# clock_module.net
KiCad netlist of a schematic drawn in EAGLE
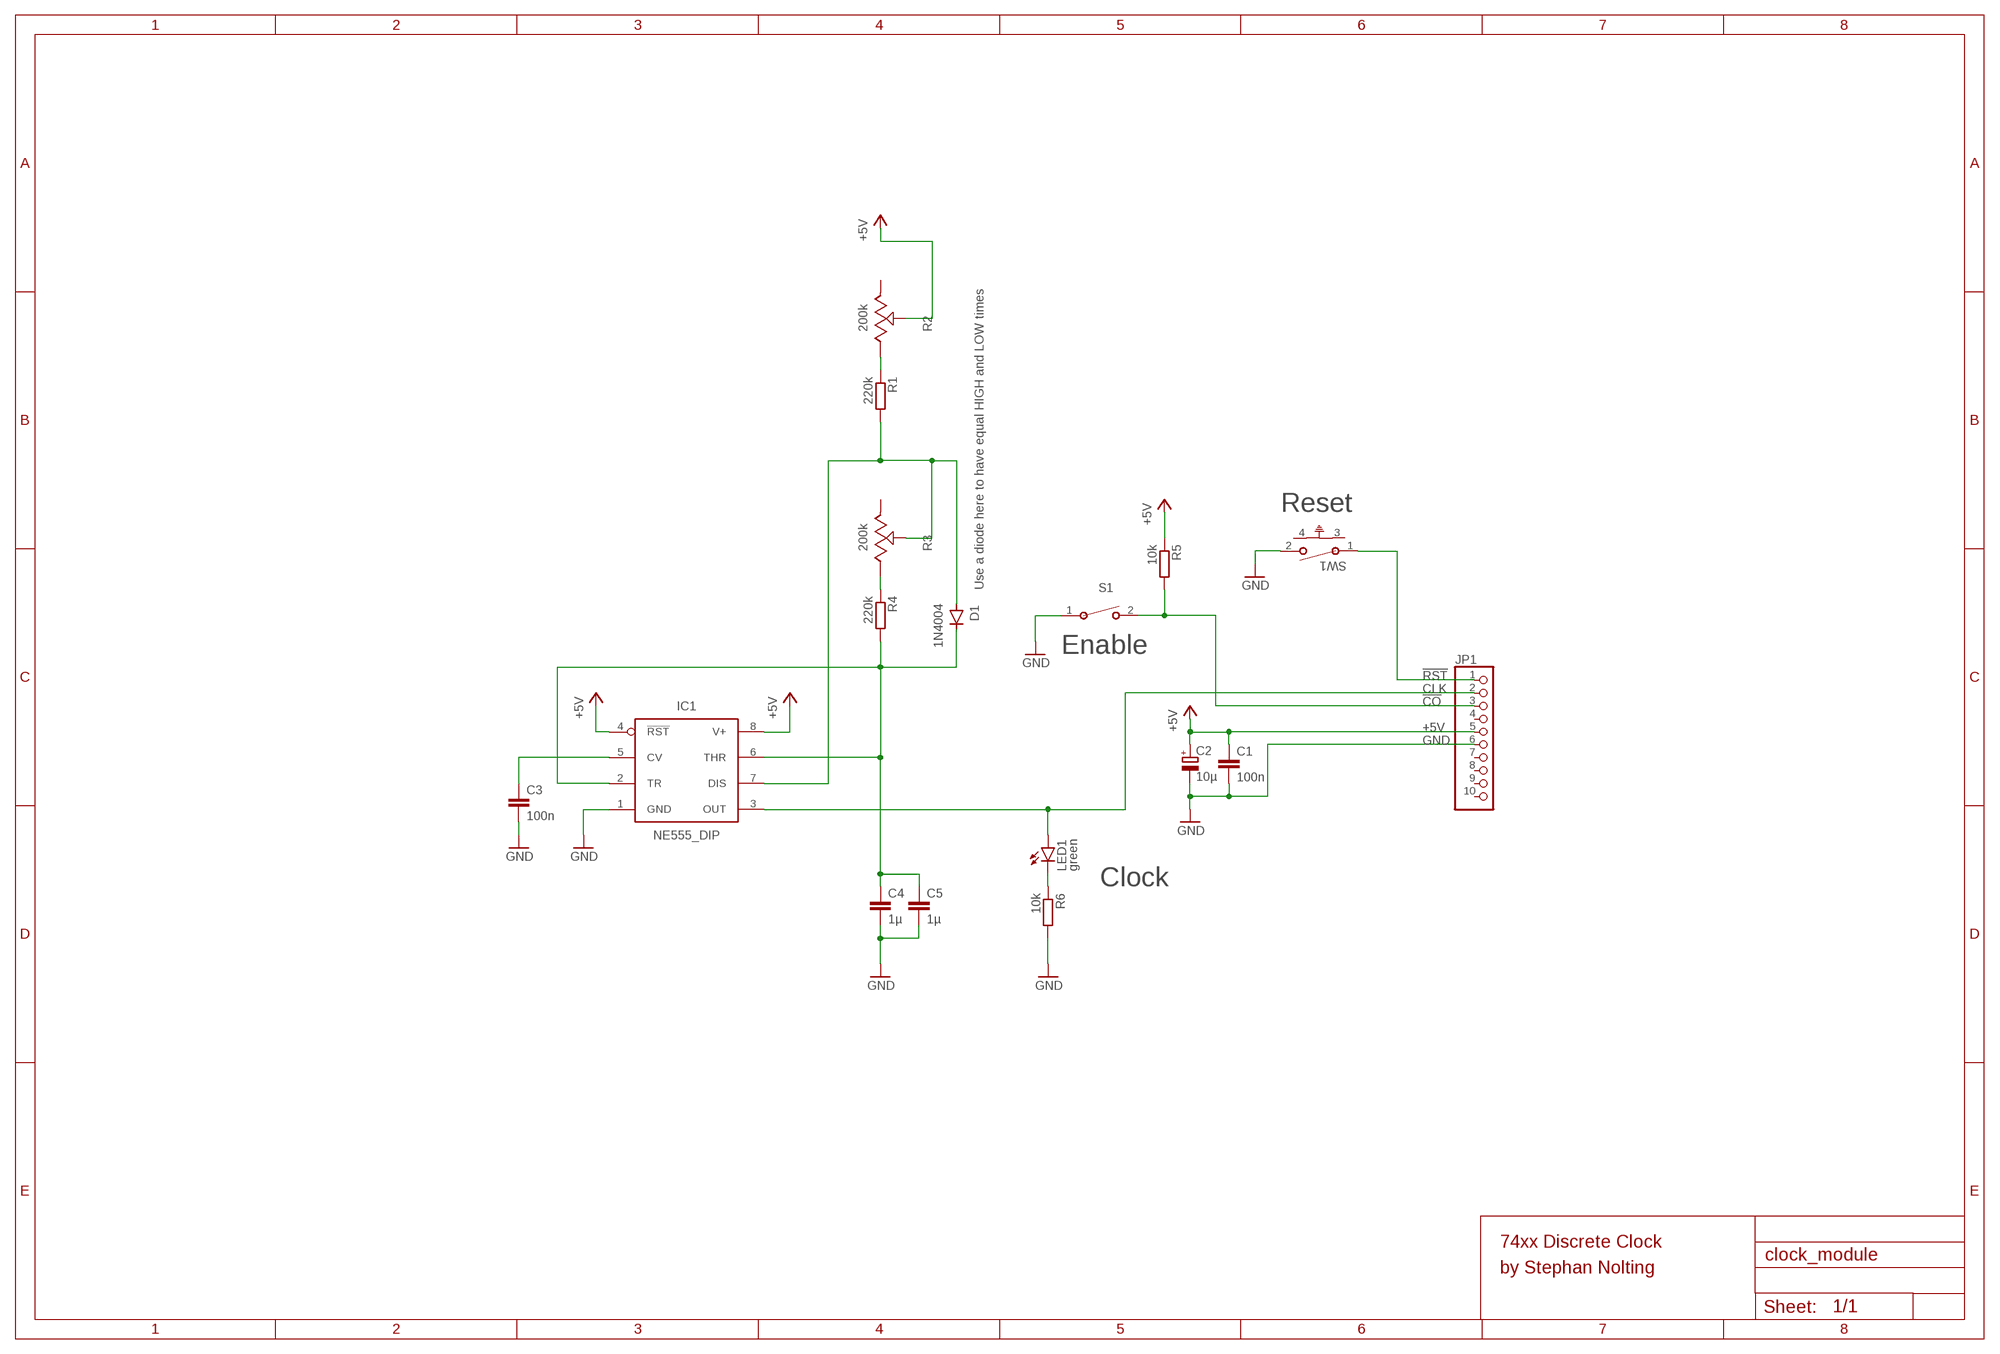
[diagram p0: schematic, sheet 1]

(export (version "E")
  (design (tool "Eeschema 10.0.6"))
  (components
    (comp (ref "C1")
      (value "100n")
      (footprint "eagle-import:C025-024X044")
      (libsource (lib "eagle-import") (part "C-EU025-024X044"))
    )
    (comp (ref "C2")
      (value "10µ")
      (footprint "eagle-import:E2-5")
      (libsource (lib "eagle-import") (part "CPOL-EUE2-5"))
    )
    (comp (ref "C3")
      (value "100n")
      (footprint "eagle-import:C025-024X044")
      (libsource (lib "eagle-import") (part "C-EU025-024X044"))
    )
    (comp (ref "C4")
      (value "1µ")
      (footprint "eagle-import:C025-024X044")
      (libsource (lib "eagle-import") (part "C-EU025-024X044"))
    )
    (comp (ref "C5")
      (value "1µ")
      (footprint "eagle-import:C025-024X044")
      (libsource (lib "eagle-import") (part "C-EU025-024X044"))
    )
    (comp (ref "D1")
      (value "1N4004")
      (footprint "eagle-import:DO-41")
      (fields
        (field (name "DIGIKEY_PART_NUMBER") "1N4004MSCT-ND")
        (field (name "MANUFACTURER") "Micro Commercial Co")
        (field (name "CREATED_BY") "PCBLayout.com")
      )
      (libsource (lib "eagle-import") (part "1N4004"))
    )
    (comp (ref "IC1")
      (value "NE555_DIP")
      (footprint "eagle-import:DIP826W53P254L959H508Q8B")
      (fields (field (name "MANUFACTURER") "Texas Instruments ") (field (name "MPN") "NE555P "))
      (libsource (lib "eagle-import") (part "555_DIPNE"))
    )
    (comp (ref "JP1")
      (value "PINHD-1X10/90")
      (footprint "eagle-import:1X10_90")
      (libsource (lib "eagle-import") (part "PINHD-1X10/90"))
    )
    (comp (ref "LED1")
      (value "green")
      (footprint "eagle-import:LED3MM")
      (libsource (lib "eagle-import") (part "LED3MM"))
    )
    (comp (ref "R1")
      (value "220k")
      (footprint "eagle-import:0204_7")
      (libsource (lib "eagle-import") (part "R-EU_0204/7"))
    )
    (comp (ref "R2")
      (value "200k")
      (footprint "eagle-import:3310Y-001-104L-ND")
      (fields
        (field (name "DIGIKEY_PARTNO") "3310Y-001-104L-ND")
        (field (name "MANUFACTURER") "Bourns Inc.")
        (field (name "MPN") "3310Y-001-104L")
        (field (name "CREATED_BY") " PCBLayout.com")
      )
      (libsource (lib "eagle-import") (part "3310Y-001-104L"))
    )
    (comp (ref "R3")
      (value "200k")
      (footprint "eagle-import:3310Y-001-104L-ND")
      (fields
        (field (name "DIGIKEY_PARTNO") "3310Y-001-104L-ND")
        (field (name "MANUFACTURER") "Bourns Inc.")
        (field (name "MPN") "3310Y-001-104L")
        (field (name "CREATED_BY") " PCBLayout.com")
      )
      (libsource (lib "eagle-import") (part "3310Y-001-104L"))
    )
    (comp (ref "R4")
      (value "220k")
      (footprint "eagle-import:0204_7")
      (libsource (lib "eagle-import") (part "R-EU_0204/7"))
    )
    (comp (ref "R5")
      (value "10k")
      (footprint "eagle-import:0204_7")
      (libsource (lib "eagle-import") (part "R-EU_0204/7"))
    )
    (comp (ref "R6")
      (value "10k")
      (footprint "eagle-import:0204_7")
      (libsource (lib "eagle-import") (part "R-EU_0204/7"))
    )
    (comp (ref "S1")
      (value "1825966-1")
      (footprint "eagle-import:SWDIP2_256X170P100")
      (fields (field (name "COPYRIGHT") "Copyright (C) 2016 Accelerated Designs. All rights reserved"))
      (libsource (lib "eagle-import") (part "1825966-1"))
    )
    (comp (ref "SW1")
      (value "1-1825027-4")
      (footprint "eagle-import:SW2_1825027-E")
      (fields (field (name "COPYRIGHT") "Copyright (C) 2016 Accelerated Designs. All rights reserved"))
      (libsource (lib "eagle-import") (part "1-1825027-4"))
    )
  )
  (nets
    (net (code "1") (name "+5V") (class "Default")
      (node (ref "C1") (pin "1") (pinfunction "1_1") (pintype "passive"))
      (node (ref "C2") (pin "+") (pinfunction "+_+") (pintype "passive"))
      (node (ref "IC1") (pin "4") (pinfunction "~{RST}_4") (pintype "input"))
      (node (ref "IC1") (pin "8") (pinfunction "V+_8") (pintype "power_in"))
      (node (ref "JP1") (pin "5") (pinfunction "5_5") (pintype "passive"))
      (node (ref "R2") (pin "2") (pinfunction "2_2") (pintype "passive"))
      (node (ref "R5") (pin "1") (pinfunction "1_1") (pintype "passive"))
    )
    (net (code "2") (name "/CLK") (class "Default")
      (node (ref "IC1") (pin "3") (pinfunction "OUT_3") (pintype "output"))
      (node (ref "JP1") (pin "2") (pinfunction "2_2") (pintype "passive"))
      (node (ref "LED1") (pin "A") (pinfunction "A_A") (pintype "passive"))
    )
    (net (code "3") (name "/~{CO}") (class "Default")
      (node (ref "JP1") (pin "3") (pinfunction "3_3") (pintype "passive"))
      (node (ref "R5") (pin "2") (pinfunction "2_2") (pintype "passive"))
      (node (ref "S1") (pin "2") (pinfunction "2_2") (pintype "passive"))
    )
    (net (code "4") (name "/~{RST}") (class "Default")
      (node (ref "JP1") (pin "1") (pinfunction "1_1") (pintype "passive"))
      (node (ref "SW1") (pin "1") (pinfunction "1_1") (pintype "passive"))
    )
    (net (code "5") (name "GND") (class "Default")
      (node (ref "C1") (pin "2") (pinfunction "2_2") (pintype "passive"))
      (node (ref "C2") (pin "-") (pinfunction "-_-") (pintype "passive"))
      (node (ref "C3") (pin "2") (pinfunction "2_2") (pintype "passive"))
      (node (ref "C4") (pin "2") (pinfunction "2_2") (pintype "passive"))
      (node (ref "C5") (pin "2") (pinfunction "2_2") (pintype "passive"))
      (node (ref "IC1") (pin "1") (pinfunction "GND_1") (pintype "power_in"))
      (node (ref "JP1") (pin "6") (pinfunction "6_6") (pintype "passive"))
      (node (ref "R6") (pin "2") (pinfunction "2_2") (pintype "passive"))
      (node (ref "S1") (pin "1") (pinfunction "1_1") (pintype "passive"))
      (node (ref "SW1") (pin "2") (pinfunction "2_2") (pintype "passive"))
    )
    (net (code "6") (name "Net-(IC1-CV)") (class "Default")
      (node (ref "C3") (pin "1") (pinfunction "1_1") (pintype "passive"))
      (node (ref "IC1") (pin "5") (pinfunction "CV_5") (pintype "input"))
    )
    (net (code "7") (name "Net-(IC1-DIS)") (class "Default")
      (node (ref "D1") (pin "A") (pinfunction "A_A") (pintype "passive"))
      (node (ref "IC1") (pin "7") (pinfunction "DIS_7") (pintype "input"))
      (node (ref "R1") (pin "2") (pinfunction "2_2") (pintype "passive"))
      (node (ref "R3") (pin "2") (pinfunction "2_2") (pintype "passive"))
    )
    (net (code "8") (name "Net-(IC1-THR)") (class "Default")
      (node (ref "C4") (pin "1") (pinfunction "1_1") (pintype "passive"))
      (node (ref "C5") (pin "1") (pinfunction "1_1") (pintype "passive"))
      (node (ref "D1") (pin "C") (pinfunction "C_C") (pintype "passive"))
      (node (ref "IC1") (pin "2") (pinfunction "TR_2") (pintype "input"))
      (node (ref "IC1") (pin "6") (pinfunction "THR_6") (pintype "input"))
      (node (ref "R4") (pin "2") (pinfunction "2_2") (pintype "passive"))
    )
    (net (code "9") (name "Net-(LED1-C)") (class "Default")
      (node (ref "LED1") (pin "K") (pinfunction "C_K") (pintype "passive"))
      (node (ref "R6") (pin "1") (pinfunction "1_1") (pintype "passive"))
    )
    (net (code "10") (name "Net-(R1-Pad1)") (class "Default")
      (node (ref "R1") (pin "1") (pinfunction "1_1") (pintype "passive"))
      (node (ref "R2") (pin "3") (pinfunction "3_3") (pintype "passive"))
    )
    (net (code "11") (name "Net-(R3-Pad3)") (class "Default")
      (node (ref "R3") (pin "3") (pinfunction "3_3") (pintype "passive"))
      (node (ref "R4") (pin "1") (pinfunction "1_1") (pintype "passive"))
    )
    (net (code "12") (name "unconnected-(JP1-Pad4)") (class "Default")
      (node (ref "JP1") (pin "4") (pinfunction "4_4") (pintype "passive"))
    )
    (net (code "13") (name "unconnected-(JP1-Pad7)") (class "Default")
      (node (ref "JP1") (pin "7") (pinfunction "7_7") (pintype "passive"))
    )
    (net (code "14") (name "unconnected-(JP1-Pad8)") (class "Default")
      (node (ref "JP1") (pin "8") (pinfunction "8_8") (pintype "passive"))
    )
    (net (code "15") (name "unconnected-(JP1-Pad9)") (class "Default")
      (node (ref "JP1") (pin "9") (pinfunction "9_9") (pintype "passive"))
    )
    (net (code "16") (name "unconnected-(JP1-Pad10)") (class "Default")
      (node (ref "JP1") (pin "10") (pinfunction "10_10") (pintype "passive"))
    )
    (net (code "17") (name "unconnected-(R2-Pad1)") (class "Default")
      (node (ref "R2") (pin "1") (pinfunction "1_1") (pintype "passive"))
    )
    (net (code "18") (name "unconnected-(R3-Pad1)") (class "Default")
      (node (ref "R3") (pin "1") (pinfunction "1_1") (pintype "passive"))
    )
    (net (code "19") (name "unconnected-(SW1-Pad3)") (class "Default")
      (node (ref "SW1") (pin "3") (pinfunction "3_3") (pintype "passive"))
    )
    (net (code "20") (name "unconnected-(SW1-Pad4)") (class "Default")
      (node (ref "SW1") (pin "4") (pinfunction "4_4") (pintype "passive"))
    )
  )
)
